# EXT_RS485.net
KiCad netlist of a schematic drawn in EAGLE
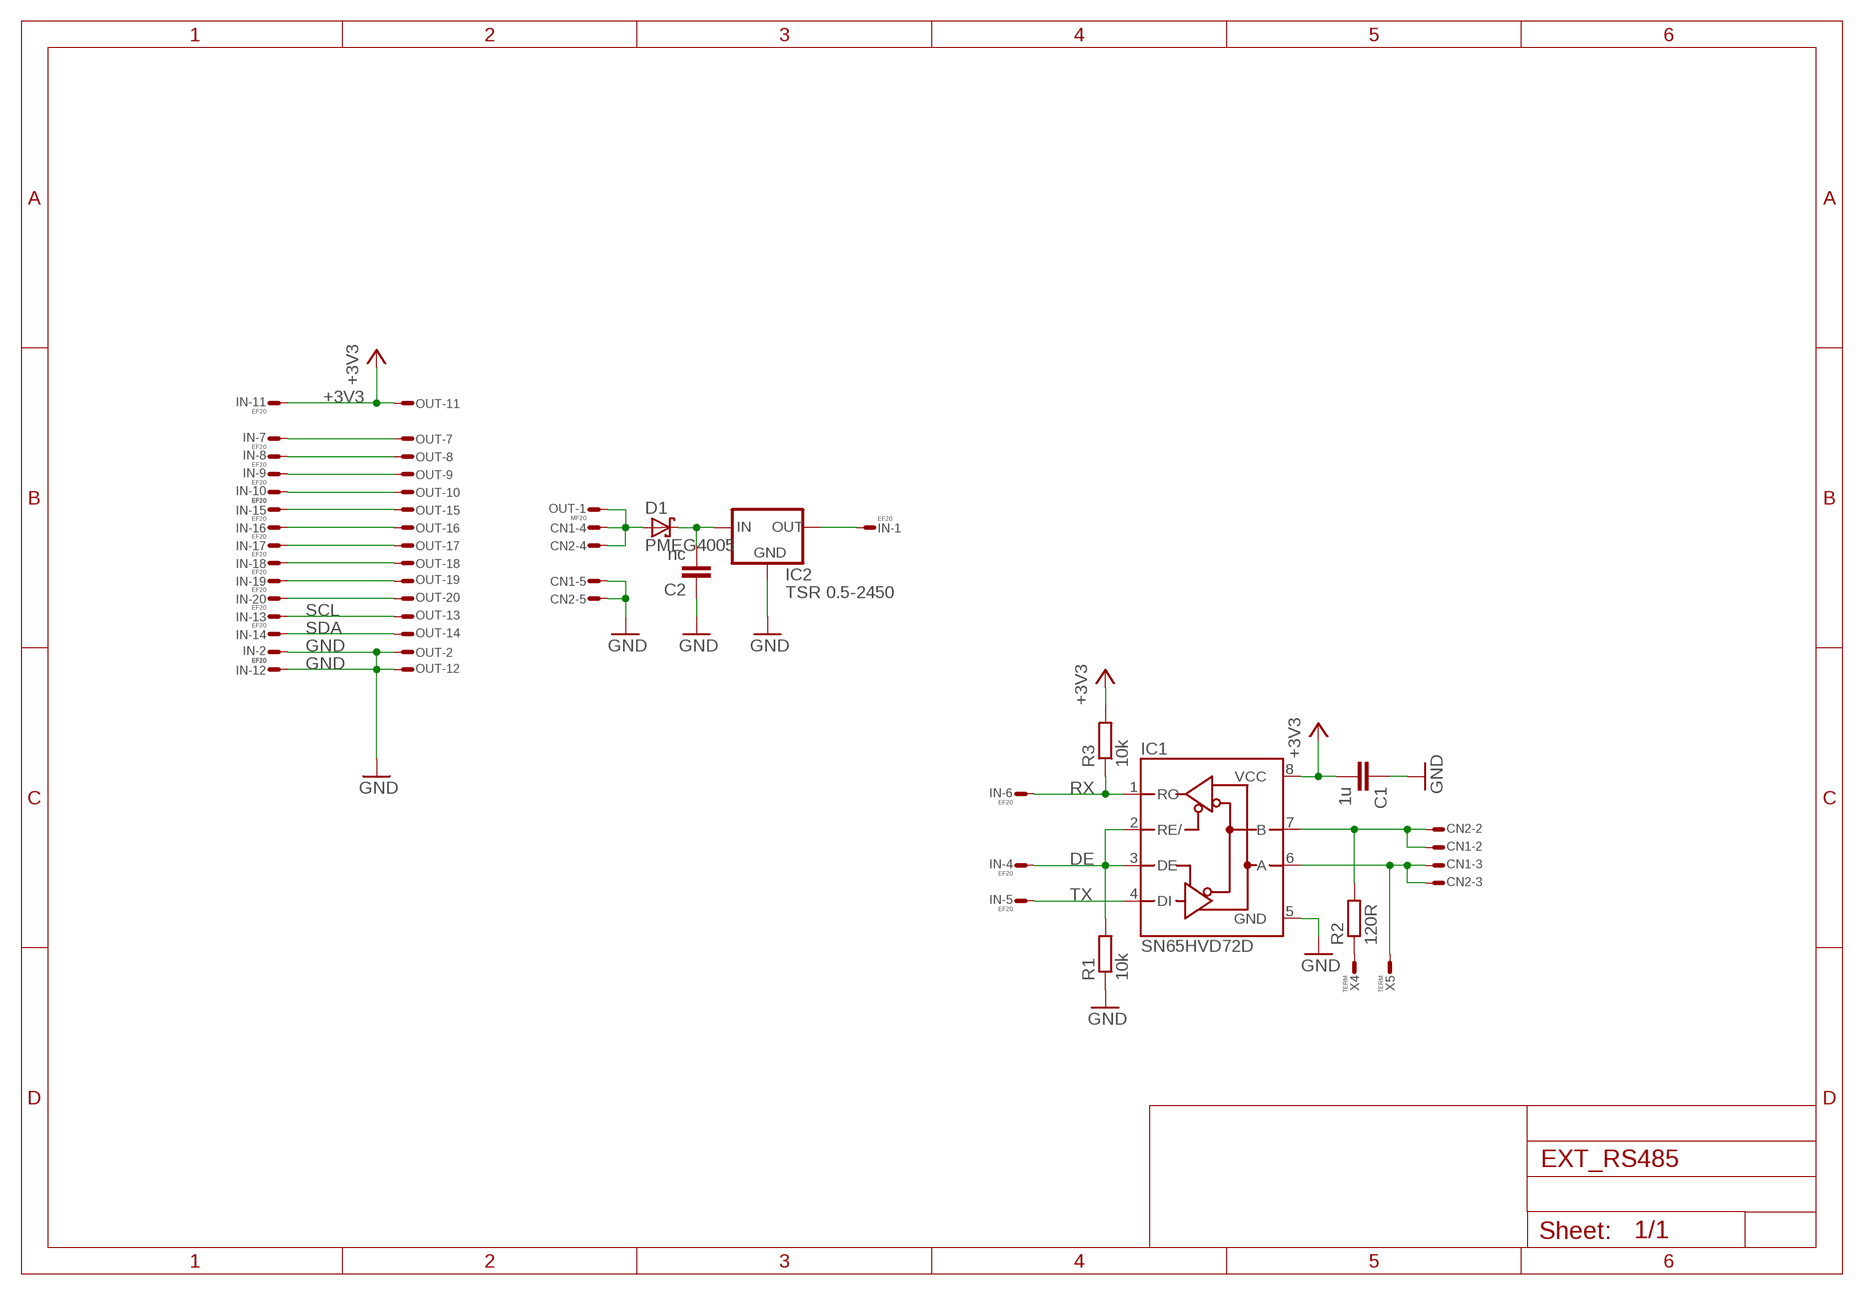
[diagram p0: schematic, sheet 1]

(export (version "E")
  (design (tool "Eeschema 10.0.6"))
  (components
    (comp (ref "C1")
      (value "1u")
      (footprint "eagle-import:0603")
      (libsource (lib "eagle-import") (part "C0603"))
    )
    (comp (ref "C2")
      (value "nc")
      (footprint "eagle-import:1206")
      (libsource (lib "eagle-import") (part "C1206"))
    )
    (comp (ref "CN1")
      (value "RJ11")
      (footprint "eagle-import:69254")
      (libsource (lib "eagle-import") (part "CON6RJ11V"))
    )
    (comp (ref "CN2")
      (value "RJ11")
      (footprint "eagle-import:69254")
      (libsource (lib "eagle-import") (part "CON6RJ11V"))
    )
    (comp (ref "D1")
      (value "PMEG4005")
      (footprint "eagle-import:SOD323")
      (libsource (lib "eagle-import") (part "D-SCHOTKY323"))
    )
    (comp (ref "IC1")
      (value "SN65HVD72D")
      (footprint "eagle-import:SOIC8")
      (libsource (lib "eagle-import") (part "MAX485"))
    )
    (comp (ref "IC2")
      (value "TSR 0.5-2450")
      (footprint "eagle-import:SIP3")
      (libsource (lib "eagle-import") (part "78XXS3"))
    )
    (comp (ref "IN")
      (value "EF20")
      (footprint "eagle-import:FE10-2WSS")
      (libsource (lib "eagle-import") (part "FE20ELSS"))
    )
    (comp (ref "OUT")
      (value "MF20")
      (footprint "eagle-import:ML20LS")
      (libsource (lib "eagle-import") (part "ML20?ELS"))
    )
    (comp (ref "R1")
      (value "10k")
      (footprint "eagle-import:0603")
      (libsource (lib "eagle-import") (part "R0603"))
    )
    (comp (ref "R2")
      (value "120R")
      (footprint "eagle-import:0603")
      (libsource (lib "eagle-import") (part "R0603"))
    )
    (comp (ref "R3")
      (value "10k")
      (footprint "eagle-import:0603")
      (libsource (lib "eagle-import") (part "R0603"))
    )
    (comp (ref "X4")
      (value "TERM")
      (footprint "eagle-import:T1.6_0.9")
      (libsource (lib "eagle-import") (part "WIREPADT1.6/0.9"))
    )
    (comp (ref "X5")
      (value "TERM")
      (footprint "eagle-import:T1.6_0.9")
      (libsource (lib "eagle-import") (part "WIREPADT1.6/0.9"))
    )
  )
  (nets
    (net (code "1") (name "+3V3") (class "Default")
      (node (ref "C1") (pin "2") (pinfunction "2_2") (pintype "passive"))
      (node (ref "IC1") (pin "8") (pinfunction "VCC_8") (pintype "bidirectional"))
      (node (ref "IN") (pin "P$11") (pinfunction "S_P$11") (pintype "passive"))
      (node (ref "OUT") (pin "P$11") (pinfunction "S_P$11") (pintype "passive"))
      (node (ref "R3") (pin "2") (pinfunction "2_2") (pintype "passive"))
    )
    (net (code "2") (name "/DE") (class "Default")
      (node (ref "IC1") (pin "2") (pinfunction "RE/_2") (pintype "bidirectional"))
      (node (ref "IC1") (pin "3") (pinfunction "DE_3") (pintype "bidirectional"))
      (node (ref "IN") (pin "P$4") (pinfunction "S_P$4") (pintype "passive"))
      (node (ref "R1") (pin "2") (pinfunction "2_2") (pintype "passive"))
    )
    (net (code "3") (name "/RX") (class "Default")
      (node (ref "IC1") (pin "1") (pinfunction "RO_1") (pintype "bidirectional"))
      (node (ref "IN") (pin "P$6") (pinfunction "S_P$6") (pintype "passive"))
      (node (ref "R3") (pin "1") (pinfunction "1_1") (pintype "passive"))
    )
    (net (code "4") (name "/SCL") (class "Default")
      (node (ref "IN") (pin "P$13") (pinfunction "S_P$13") (pintype "passive"))
      (node (ref "OUT") (pin "P$13") (pinfunction "S_P$13") (pintype "passive"))
    )
    (net (code "5") (name "/SDA") (class "Default")
      (node (ref "IN") (pin "P$14") (pinfunction "S_P$14") (pintype "passive"))
      (node (ref "OUT") (pin "P$14") (pinfunction "S_P$14") (pintype "passive"))
    )
    (net (code "6") (name "/TX") (class "Default")
      (node (ref "IC1") (pin "4") (pinfunction "DI_4") (pintype "bidirectional"))
      (node (ref "IN") (pin "P$5") (pinfunction "S_P$5") (pintype "passive"))
    )
    (net (code "7") (name "GND") (class "Default")
      (node (ref "C1") (pin "1") (pinfunction "1_1") (pintype "passive"))
      (node (ref "C2") (pin "1") (pinfunction "1_1") (pintype "passive"))
      (node (ref "CN1") (pin "-5") (pinfunction "S_-5") (pintype "passive"))
      (node (ref "CN2") (pin "-5") (pinfunction "S_-5") (pintype "passive"))
      (node (ref "IC1") (pin "5") (pinfunction "GND_5") (pintype "bidirectional"))
      (node (ref "IC2") (pin "P$2") (pinfunction "GND_P$2") (pintype "input"))
      (node (ref "IN") (pin "P$12") (pinfunction "S_P$12") (pintype "passive"))
      (node (ref "IN") (pin "P$2") (pinfunction "S_P$2") (pintype "passive"))
      (node (ref "OUT") (pin "P$12") (pinfunction "S_P$12") (pintype "passive"))
      (node (ref "OUT") (pin "P$2") (pinfunction "S_P$2") (pintype "passive"))
      (node (ref "R1") (pin "1") (pinfunction "1_1") (pintype "passive"))
    )
    (net (code "8") (name "Net-(CN1B-S)") (class "Default")
      (node (ref "CN1") (pin "-2") (pinfunction "S_-2") (pintype "passive"))
      (node (ref "CN2") (pin "-2") (pinfunction "S_-2") (pintype "passive"))
      (node (ref "IC1") (pin "7") (pinfunction "B_7") (pintype "bidirectional"))
      (node (ref "R2") (pin "2") (pinfunction "2_2") (pintype "passive"))
    )
    (net (code "9") (name "Net-(CN1C-S)") (class "Default")
      (node (ref "CN1") (pin "-3") (pinfunction "S_-3") (pintype "passive"))
      (node (ref "CN2") (pin "-3") (pinfunction "S_-3") (pintype "passive"))
      (node (ref "IC1") (pin "6") (pinfunction "A_6") (pintype "bidirectional"))
      (node (ref "X5") (pin "1") (pinfunction "S_1") (pintype "passive"))
    )
    (net (code "10") (name "Net-(CN1D-S)") (class "Default")
      (node (ref "CN1") (pin "-4") (pinfunction "S_-4") (pintype "passive"))
      (node (ref "CN2") (pin "-4") (pinfunction "S_-4") (pintype "passive"))
      (node (ref "D1") (pin "A") (pinfunction "A_A") (pintype "passive"))
      (node (ref "OUT") (pin "P$1") (pinfunction "S_P$1") (pintype "passive"))
    )
    (net (code "11") (name "Net-(IC2-IN)") (class "Default")
      (node (ref "C2") (pin "2") (pinfunction "2_2") (pintype "passive"))
      (node (ref "D1") (pin "C") (pinfunction "C_C") (pintype "passive"))
      (node (ref "IC2") (pin "P$1") (pinfunction "IN_P$1") (pintype "input"))
    )
    (net (code "12") (name "Net-(IC2-OUT)") (class "Default")
      (node (ref "IC2") (pin "P$3") (pinfunction "OUT_P$3") (pintype "passive"))
      (node (ref "IN") (pin "P$1") (pinfunction "S_P$1") (pintype "passive"))
    )
    (net (code "13") (name "Net-(INB-S)") (class "Default")
      (node (ref "IN") (pin "P$10") (pinfunction "S_P$10") (pintype "passive"))
      (node (ref "OUT") (pin "P$10") (pinfunction "S_P$10") (pintype "passive"))
    )
    (net (code "14") (name "Net-(ING-S)") (class "Default")
      (node (ref "IN") (pin "P$15") (pinfunction "S_P$15") (pintype "passive"))
      (node (ref "OUT") (pin "P$15") (pinfunction "S_P$15") (pintype "passive"))
    )
    (net (code "15") (name "Net-(INH-S)") (class "Default")
      (node (ref "IN") (pin "P$16") (pinfunction "S_P$16") (pintype "passive"))
      (node (ref "OUT") (pin "P$16") (pinfunction "S_P$16") (pintype "passive"))
    )
    (net (code "16") (name "Net-(INI-S)") (class "Default")
      (node (ref "IN") (pin "P$17") (pinfunction "S_P$17") (pintype "passive"))
      (node (ref "OUT") (pin "P$17") (pinfunction "S_P$17") (pintype "passive"))
    )
    (net (code "17") (name "Net-(INJ-S)") (class "Default")
      (node (ref "IN") (pin "P$18") (pinfunction "S_P$18") (pintype "passive"))
      (node (ref "OUT") (pin "P$18") (pinfunction "S_P$18") (pintype "passive"))
    )
    (net (code "18") (name "Net-(INK-S)") (class "Default")
      (node (ref "IN") (pin "P$19") (pinfunction "S_P$19") (pintype "passive"))
      (node (ref "OUT") (pin "P$19") (pinfunction "S_P$19") (pintype "passive"))
    )
    (net (code "19") (name "Net-(INM-S)") (class "Default")
      (node (ref "IN") (pin "P$20") (pinfunction "S_P$20") (pintype "passive"))
      (node (ref "OUT") (pin "P$20") (pinfunction "S_P$20") (pintype "passive"))
    )
    (net (code "20") (name "Net-(INR-S)") (class "Default")
      (node (ref "IN") (pin "P$7") (pinfunction "S_P$7") (pintype "passive"))
      (node (ref "OUT") (pin "P$7") (pinfunction "S_P$7") (pintype "passive"))
    )
    (net (code "21") (name "Net-(INS-S)") (class "Default")
      (node (ref "IN") (pin "P$8") (pinfunction "S_P$8") (pintype "passive"))
      (node (ref "OUT") (pin "P$8") (pinfunction "S_P$8") (pintype "passive"))
    )
    (net (code "22") (name "Net-(INT-S)") (class "Default")
      (node (ref "IN") (pin "P$9") (pinfunction "S_P$9") (pintype "passive"))
      (node (ref "OUT") (pin "P$9") (pinfunction "S_P$9") (pintype "passive"))
    )
    (net (code "23") (name "Net-(X4-S)") (class "Default")
      (node (ref "R2") (pin "1") (pinfunction "1_1") (pintype "passive"))
      (node (ref "X4") (pin "1") (pinfunction "S_1") (pintype "passive"))
    )
  )
)
